# design.net
KiCad netlist of a schematic drawn in Altium Designer
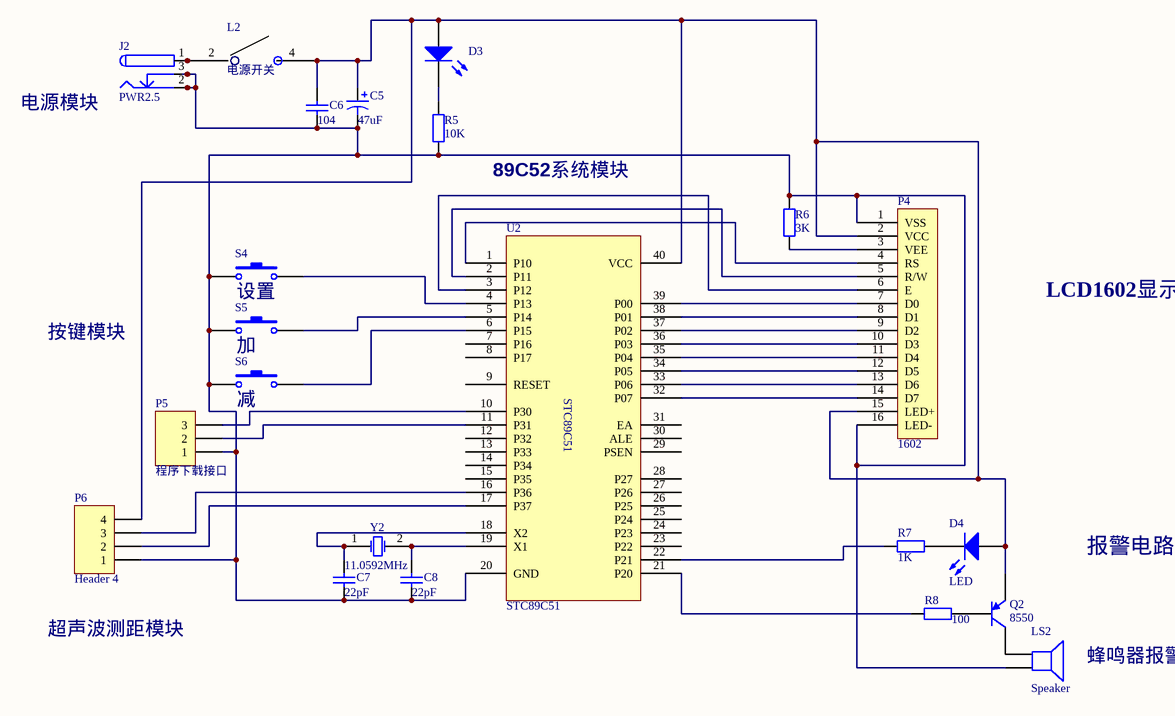
[diagram p0: 线连接图纸.SchDoc]

(export (version "E")
  (design (tool "Eeschema 10.0.6"))
  (components
    (comp (ref "C5")
      (value "47uF")
      (footprint "CAP-100")
      (description "Polarized Capacitor (Radial)")
      (fields (field (name "PUBLISHER") "Altium Limited"))
      (libsource (lib "Miscellaneous Devices") (part "Cap Pol1"))
    )
    (comp (ref "C6")
      (value "104")
      (footprint "CAP")
      (description "Capacitor")
      (fields (field (name "PUBLISHER") "Altium Limited"))
      (libsource (lib "Miscellaneous Devices") (part "Cap"))
    )
    (comp (ref "C7")
      (value "22pF")
      (footprint "CAP")
      (description "Capacitor")
      (fields (field (name "PUBLISHER") "Altium Limited"))
      (libsource (lib "Miscellaneous Devices") (part "Cap"))
    )
    (comp (ref "C8")
      (value "22pF")
      (footprint "CAP")
      (description "Capacitor")
      (fields (field (name "PUBLISHER") "Altium Limited"))
      (libsource (lib "Miscellaneous Devices") (part "Cap"))
    )
    (comp (ref "D3")
      (value "LED")
      (footprint "LED")
      (description "Typical INFRARED GaAs LED")
      (fields (field (name "PUBLISHER") "Altium Limited"))
      (libsource (lib "Miscellaneous Devices") (part "LED0"))
    )
    (comp (ref "D4")
      (value "LED")
      (footprint "LED")
      (description "Typical INFRARED GaAs LED")
      (fields (field (name "PUBLISHER") "Altium Limited"))
      (libsource (lib "Miscellaneous Devices") (part "LED0"))
    )
    (comp (ref "J2")
      (value "PWR2.5")
      (footprint "POWER")
      (description "Low Voltage Power Supply Connector")
      (fields (field (name "PUBLISHER") "Altium Limited"))
      (libsource (lib "Miscellaneous Connectors") (part "PWR2.5"))
    )
    (comp (ref "L2") (value "电源开关") (footprint "SWITCH") (libsource (lib "元件原理图") (part "Liujiao")))
    (comp (ref "LS2")
      (value "Speaker")
      (footprint "SPEAK")
      (description "Loudspeaker")
      (fields (field (name "PUBLISHER") "Altium Limited"))
      (libsource (lib "Miscellaneous Devices") (part "Speaker"))
    )
    (comp (ref "P4") (value "1602") (footprint "lcd1602") (libsource (lib "元件原理图") (part "1602")))
    (comp (ref "P5")
      (value "程序下载接口")
      (footprint "HDR1X3")
      (description "Header, 3-Pin")
      (fields (field (name "PUBLISHER") "Altium Limited"))
      (libsource (lib "Miscellaneous Connectors") (part "Header 3"))
    )
    (comp (ref "P6")
      (value "Header 4")
      (footprint "HDR1X4")
      (description "Header, 4-Pin")
      (fields (field (name "PUBLISHER") "Altium Limited"))
      (libsource (lib "Miscellaneous Connectors") (part "Header 4"))
    )
    (comp (ref "Q2")
      (value "8550")
      (footprint "TO-92A")
      (description "PNP General Purpose Amplifier")
      (fields (field (name "PUBLISHER") "Altium Limited"))
      (libsource (lib "Miscellaneous Devices") (part "2N3906"))
    )
    (comp (ref "R5")
      (value "10K")
      (footprint "RES")
      (description "Resistor")
      (fields (field (name "PUBLISHER") "Altium Limited"))
      (libsource (lib "Miscellaneous Devices") (part "Res2"))
    )
    (comp (ref "R6")
      (value "3K")
      (footprint "RES")
      (description "Resistor")
      (fields (field (name "PUBLISHER") "Altium Limited"))
      (libsource (lib "Miscellaneous Devices") (part "Res2"))
    )
    (comp (ref "R7")
      (value "1K")
      (footprint "RES")
      (description "Resistor")
      (fields (field (name "PUBLISHER") "Altium Limited"))
      (libsource (lib "") (part "Res2_1"))
    )
    (comp (ref "R8")
      (value "100")
      (footprint "RES")
      (description "Resistor")
      (fields (field (name "PUBLISHER") "Altium Limited"))
      (libsource (lib "") (part "Res2_1"))
    )
    (comp (ref "S4")
      (value "~")
      (footprint "KEY")
      (description "Switch")
      (fields (field (name "PUBLISHER") "Altium Limited"))
      (libsource (lib "Miscellaneous Devices") (part "SW-PB"))
    )
    (comp (ref "S5")
      (value "~")
      (footprint "KEY")
      (description "Switch")
      (fields (field (name "PUBLISHER") "Altium Limited"))
      (libsource (lib "Miscellaneous Devices") (part "SW-PB"))
    )
    (comp (ref "S6")
      (value "~")
      (footprint "KEY")
      (description "Switch")
      (fields (field (name "PUBLISHER") "Altium Limited"))
      (libsource (lib "Miscellaneous Devices") (part "SW-PB"))
    )
    (comp (ref "U2") (value "STC89C51") (footprint "DIP40") (libsource (lib "元件原理图") (part "STC89C52")))
    (comp (ref "Y2")
      (value "11.0592MHz")
      (footprint "XTAL200")
      (description "Crystal Oscillator")
      (fields (field (name "PUBLISHER") "Altium Limited"))
      (libsource (lib "Miscellaneous Devices") (part "XTAL"))
    )
  )
  (nets
    (net (code "1") (name "Net-(D3-A)") (class "Default")
      (node (ref "C5") (pin "1") (pinfunction "1_1") (pintype "passive"))
      (node (ref "C6") (pin "2") (pinfunction "2_2") (pintype "passive"))
      (node (ref "D3") (pin "1") (pinfunction "A_1") (pintype "passive"))
      (node (ref "D4") (pin "1") (pinfunction "A_1") (pintype "passive"))
      (node (ref "L2") (pin "4") (pinfunction "0_4") (pintype "passive"))
      (node (ref "P4") (pin "15") (pinfunction "LED+_15") (pintype "passive"))
      (node (ref "P4") (pin "2") (pinfunction "VCC_2") (pintype "passive"))
      (node (ref "P6") (pin "4") (pinfunction "4_4") (pintype "passive"))
      (node (ref "Q2") (pin "1") (pinfunction "E_1") (pintype "passive"))
      (node (ref "U2") (pin "40") (pinfunction "VCC_40") (pintype "passive"))
    )
    (net (code "2") (name "Net-(D3-K)") (class "Default")
      (node (ref "D3") (pin "2") (pinfunction "K_2") (pintype "passive"))
      (node (ref "R5") (pin "2") (pinfunction "2_2") (pintype "passive"))
    )
    (net (code "3") (name "Net-(D4-K)") (class "Default")
      (node (ref "D4") (pin "2") (pinfunction "K_2") (pintype "passive"))
      (node (ref "R7") (pin "2") (pinfunction "2_2") (pintype "passive"))
    )
    (net (code "4") (name "Net-(L2-1)") (class "Default")
      (node (ref "J2") (pin "1") (pinfunction "1_1") (pintype "power_in"))
      (node (ref "J2") (pin "1A") (pinfunction "1A_1A") (pintype "power_in"))
      (node (ref "J2") (pin "1B") (pinfunction "1B_1B") (pintype "power_in"))
      (node (ref "L2") (pin "2") (pinfunction "1_2") (pintype "passive"))
    )
    (net (code "5") (name "Net-(P4-D0)") (class "Default")
      (node (ref "P4") (pin "7") (pinfunction "D0_7") (pintype "passive"))
      (node (ref "U2") (pin "39") (pinfunction "P00_39") (pintype "passive"))
    )
    (net (code "6") (name "Net-(P4-D1)") (class "Default")
      (node (ref "P4") (pin "8") (pinfunction "D1_8") (pintype "passive"))
      (node (ref "U2") (pin "38") (pinfunction "P01_38") (pintype "passive"))
    )
    (net (code "7") (name "Net-(P4-D2)") (class "Default")
      (node (ref "P4") (pin "9") (pinfunction "D2_9") (pintype "passive"))
      (node (ref "U2") (pin "37") (pinfunction "P02_37") (pintype "passive"))
    )
    (net (code "8") (name "Net-(P4-D3)") (class "Default")
      (node (ref "P4") (pin "10") (pinfunction "D3_10") (pintype "passive"))
      (node (ref "U2") (pin "36") (pinfunction "P03_36") (pintype "passive"))
    )
    (net (code "9") (name "Net-(P4-D4)") (class "Default")
      (node (ref "P4") (pin "11") (pinfunction "D4_11") (pintype "passive"))
      (node (ref "U2") (pin "35") (pinfunction "P04_35") (pintype "passive"))
    )
    (net (code "10") (name "Net-(P4-D5)") (class "Default")
      (node (ref "P4") (pin "12") (pinfunction "D5_12") (pintype "passive"))
      (node (ref "U2") (pin "34") (pinfunction "P05_34") (pintype "passive"))
    )
    (net (code "11") (name "Net-(P4-D6)") (class "Default")
      (node (ref "P4") (pin "13") (pinfunction "D6_13") (pintype "passive"))
      (node (ref "U2") (pin "33") (pinfunction "P06_33") (pintype "passive"))
    )
    (net (code "12") (name "Net-(P4-D7)") (class "Default")
      (node (ref "P4") (pin "14") (pinfunction "D7_14") (pintype "passive"))
      (node (ref "U2") (pin "32") (pinfunction "P07_32") (pintype "passive"))
    )
    (net (code "13") (name "Net-(P4-E)") (class "Default")
      (node (ref "P4") (pin "6") (pinfunction "E_6") (pintype "passive"))
      (node (ref "U2") (pin "3") (pinfunction "P12_3") (pintype "passive"))
    )
    (net (code "14") (name "Net-(P4-LED-)") (class "Default")
      (node (ref "C5") (pin "2") (pinfunction "2_2") (pintype "passive"))
      (node (ref "C6") (pin "1") (pinfunction "1_1") (pintype "passive"))
      (node (ref "C7") (pin "1") (pinfunction "1_1") (pintype "passive"))
      (node (ref "C8") (pin "1") (pinfunction "1_1") (pintype "passive"))
      (node (ref "J2") (pin "2") (pinfunction "2_2") (pintype "power_in"))
      (node (ref "J2") (pin "2A") (pinfunction "2A_2A") (pintype "power_in"))
      (node (ref "J2") (pin "2B") (pinfunction "2B_2B") (pintype "power_in"))
      (node (ref "J2") (pin "3") (pinfunction "3_3") (pintype "power_in"))
      (node (ref "J2") (pin "3A") (pinfunction "3A_3A") (pintype "power_in"))
      (node (ref "J2") (pin "3B") (pinfunction "3B_3B") (pintype "power_in"))
      (node (ref "LS2") (pin "2") (pinfunction "2_2") (pintype "passive"))
      (node (ref "P4") (pin "1") (pinfunction "VSS_1") (pintype "passive"))
      (node (ref "P4") (pin "16") (pinfunction "LED-_16") (pintype "passive"))
      (node (ref "P5") (pin "1") (pinfunction "1_1") (pintype "passive"))
      (node (ref "P6") (pin "1") (pinfunction "1_1") (pintype "passive"))
      (node (ref "R5") (pin "1") (pinfunction "1_1") (pintype "passive"))
      (node (ref "R6") (pin "2") (pinfunction "2_2") (pintype "passive"))
      (node (ref "S4") (pin "1") (pinfunction "1_1") (pintype "passive"))
      (node (ref "S5") (pin "1") (pinfunction "1_1") (pintype "passive"))
      (node (ref "S6") (pin "1") (pinfunction "1_1") (pintype "passive"))
      (node (ref "U2") (pin "20") (pinfunction "GND_20") (pintype "passive"))
    )
    (net (code "15") (name "Net-(P4-RS)") (class "Default")
      (node (ref "P4") (pin "4") (pinfunction "RS_4") (pintype "passive"))
      (node (ref "U2") (pin "1") (pinfunction "P10_1") (pintype "passive"))
    )
    (net (code "16") (name "Net-(P4-R{slash}W)") (class "Default")
      (node (ref "P4") (pin "5") (pinfunction "R/W_5") (pintype "passive"))
      (node (ref "U2") (pin "2") (pinfunction "P11_2") (pintype "passive"))
    )
    (net (code "17") (name "Net-(P4-VEE)") (class "Default")
      (node (ref "P4") (pin "3") (pinfunction "VEE_3") (pintype "passive"))
      (node (ref "R6") (pin "1") (pinfunction "1_1") (pintype "passive"))
    )
    (net (code "18") (name "Net-(Q2-B)") (class "Default")
      (node (ref "Q2") (pin "2") (pinfunction "B_2") (pintype "passive"))
      (node (ref "R8") (pin "2") (pinfunction "2_2") (pintype "passive"))
    )
    (net (code "19") (name "Net-(Q2-C)") (class "Default")
      (node (ref "LS2") (pin "1") (pinfunction "1_1") (pintype "passive"))
      (node (ref "Q2") (pin "3") (pinfunction "C_3") (pintype "passive"))
    )
    (net (code "20") (name "Net-(U2-P13)") (class "Default")
      (node (ref "S4") (pin "2") (pinfunction "2_2") (pintype "passive"))
      (node (ref "U2") (pin "4") (pinfunction "P13_4") (pintype "passive"))
    )
    (net (code "21") (name "Net-(U2-P14)") (class "Default")
      (node (ref "S5") (pin "2") (pinfunction "2_2") (pintype "passive"))
      (node (ref "U2") (pin "5") (pinfunction "P14_5") (pintype "passive"))
    )
    (net (code "22") (name "Net-(U2-P15)") (class "Default")
      (node (ref "S6") (pin "2") (pinfunction "2_2") (pintype "passive"))
      (node (ref "U2") (pin "6") (pinfunction "P15_6") (pintype "passive"))
    )
    (net (code "23") (name "Net-(U2-P20)") (class "Default")
      (node (ref "R8") (pin "1") (pinfunction "1_1") (pintype "passive"))
      (node (ref "U2") (pin "21") (pinfunction "P20_21") (pintype "passive"))
    )
    (net (code "24") (name "Net-(U2-P21)") (class "Default")
      (node (ref "R7") (pin "1") (pinfunction "1_1") (pintype "passive"))
      (node (ref "U2") (pin "22") (pinfunction "P21_22") (pintype "passive"))
    )
    (net (code "25") (name "Net-(U2-P30)") (class "Default")
      (node (ref "P5") (pin "3") (pinfunction "3_3") (pintype "passive"))
      (node (ref "U2") (pin "10") (pinfunction "P30_10") (pintype "passive"))
    )
    (net (code "26") (name "Net-(U2-P31)") (class "Default")
      (node (ref "P5") (pin "2") (pinfunction "2_2") (pintype "passive"))
      (node (ref "U2") (pin "11") (pinfunction "P31_11") (pintype "passive"))
    )
    (net (code "27") (name "Net-(U2-P36)") (class "Default")
      (node (ref "P6") (pin "3") (pinfunction "3_3") (pintype "passive"))
      (node (ref "U2") (pin "16") (pinfunction "P36_16") (pintype "passive"))
    )
    (net (code "28") (name "Net-(U2-P37)") (class "Default")
      (node (ref "P6") (pin "2") (pinfunction "2_2") (pintype "passive"))
      (node (ref "U2") (pin "17") (pinfunction "P37_17") (pintype "passive"))
    )
    (net (code "29") (name "Net-(U2-X1)") (class "Default")
      (node (ref "C8") (pin "2") (pinfunction "2_2") (pintype "passive"))
      (node (ref "U2") (pin "19") (pinfunction "X1_19") (pintype "passive"))
      (node (ref "Y2") (pin "2") (pinfunction "OSC2_2") (pintype "passive"))
    )
    (net (code "30") (name "Net-(U2-X2)") (class "Default")
      (node (ref "C7") (pin "2") (pinfunction "2_2") (pintype "passive"))
      (node (ref "U2") (pin "18") (pinfunction "X2_18") (pintype "passive"))
      (node (ref "Y2") (pin "1") (pinfunction "OSC1_1") (pintype "passive"))
    )
    (net (code "31") (name "unconnected-(U2-ALE-Pad30)") (class "Default")
      (node (ref "U2") (pin "30") (pinfunction "ALE_30") (pintype "passive"))
    )
    (net (code "32") (name "unconnected-(U2-EA-Pad31)") (class "Default")
      (node (ref "U2") (pin "31") (pinfunction "EA_31") (pintype "passive"))
    )
    (net (code "33") (name "unconnected-(U2-P16-Pad7)") (class "Default")
      (node (ref "U2") (pin "7") (pinfunction "P16_7") (pintype "passive"))
    )
    (net (code "34") (name "unconnected-(U2-P17-Pad8)") (class "Default")
      (node (ref "U2") (pin "8") (pinfunction "P17_8") (pintype "passive"))
    )
    (net (code "35") (name "unconnected-(U2-P22-Pad23)") (class "Default")
      (node (ref "U2") (pin "23") (pinfunction "P22_23") (pintype "passive"))
    )
    (net (code "36") (name "unconnected-(U2-P23-Pad24)") (class "Default")
      (node (ref "U2") (pin "24") (pinfunction "P23_24") (pintype "passive"))
    )
    (net (code "37") (name "unconnected-(U2-P24-Pad25)") (class "Default")
      (node (ref "U2") (pin "25") (pinfunction "P24_25") (pintype "passive"))
    )
    (net (code "38") (name "unconnected-(U2-P25-Pad26)") (class "Default")
      (node (ref "U2") (pin "26") (pinfunction "P25_26") (pintype "passive"))
    )
    (net (code "39") (name "unconnected-(U2-P26-Pad27)") (class "Default")
      (node (ref "U2") (pin "27") (pinfunction "P26_27") (pintype "passive"))
    )
    (net (code "40") (name "unconnected-(U2-P27-Pad28)") (class "Default")
      (node (ref "U2") (pin "28") (pinfunction "P27_28") (pintype "passive"))
    )
    (net (code "41") (name "unconnected-(U2-P32-Pad12)") (class "Default")
      (node (ref "U2") (pin "12") (pinfunction "P32_12") (pintype "passive"))
    )
    (net (code "42") (name "unconnected-(U2-P33-Pad13)") (class "Default")
      (node (ref "U2") (pin "13") (pinfunction "P33_13") (pintype "passive"))
    )
    (net (code "43") (name "unconnected-(U2-P34-Pad14)") (class "Default")
      (node (ref "U2") (pin "14") (pinfunction "P34_14") (pintype "passive"))
    )
    (net (code "44") (name "unconnected-(U2-P35-Pad15)") (class "Default")
      (node (ref "U2") (pin "15") (pinfunction "P35_15") (pintype "passive"))
    )
    (net (code "45") (name "unconnected-(U2-PSEN-Pad29)") (class "Default")
      (node (ref "U2") (pin "29") (pinfunction "PSEN_29") (pintype "passive"))
    )
    (net (code "46") (name "unconnected-(U2-RESET-Pad9)") (class "Default")
      (node (ref "U2") (pin "9") (pinfunction "RESET_9") (pintype "passive"))
    )
  )
)
